# ISO_INPUT.net
KiCad netlist of a schematic drawn in Altium Designer
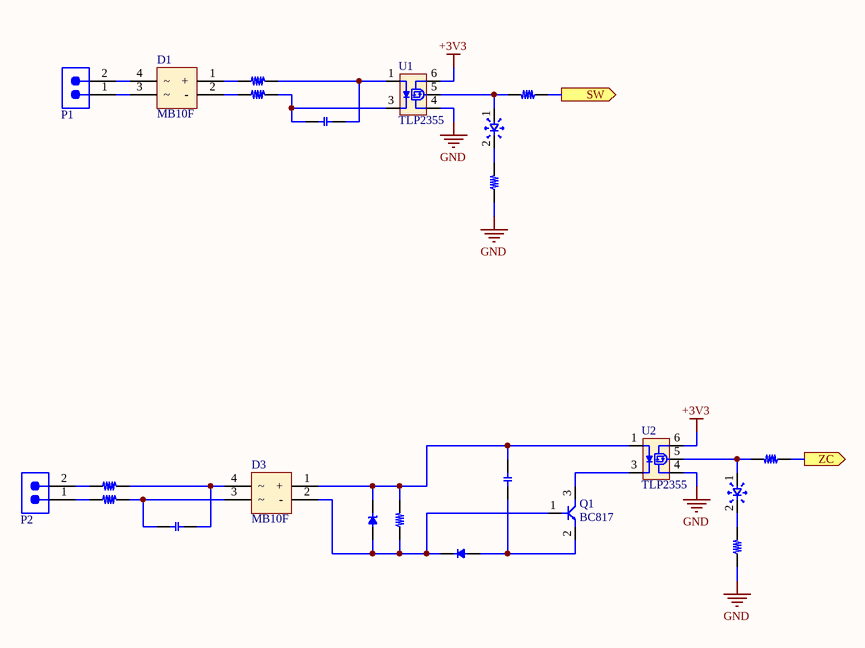
[diagram p0: ISO_INPUT.SchDoc]

(export (version "E")
  (design (tool "Eeschema 10.0.6"))
  (components
    (comp (ref "C1")
      (value "CAP_SMD")
      (footprint "C 1206")
      (libsource (lib "radmehr_library") (part "CAP_SMD"))
    )
    (comp (ref "C2")
      (value "CAP_SMD")
      (footprint "C 1206")
      (libsource (lib "radmehr_library") (part "CAP_SMD"))
    )
    (comp (ref "C3")
      (value "CAP_SMD")
      (footprint "C 1206")
      (libsource (lib "radmehr_library") (part "CAP_SMD"))
    )
    (comp (ref "D1") (value "MB10F") (footprint "MBF") (libsource (lib "radmehr_library") (part "MB10F")))
    (comp (ref "D2")
      (value "LED_SMD")
      (footprint "D 0603")
      (libsource (lib "radmehr_library") (part "LED_SMD"))
    )
    (comp (ref "D3") (value "MB10F") (footprint "MBF") (libsource (lib "radmehr_library") (part "MB10F")))
    (comp (ref "D4")
      (value "LED_SMD")
      (footprint "D 0603")
      (libsource (lib "radmehr_library") (part "LED_SMD"))
    )
    (comp (ref "D5")
      (value "DIOD_SMD_ZENER")
      (footprint "DIOD_SMA")
      (libsource (lib "radmehr_library") (part "DIOD_SMD_ZENER"))
    )
    (comp (ref "D6")
      (value "DIOD_SMD")
      (footprint "DIOD_SMA")
      (libsource (lib "radmehr_library") (part "DIOD_SMD"))
    )
    (comp (ref "P1")
      (value "691321300002")
      (footprint "691321300002")
      (description "WR-TBL Series 321 Vertical PCB Header, Through Hole, pitch 3.81mm, 2p")
      (fields (field (name "MANUFACTURER") "Wurth Elektronik"))
      (libsource (lib "Altium_WR-TBL (rev22a)") (part "691321300002"))
    )
    (comp (ref "P2")
      (value "691321300002")
      (footprint "691321300002")
      (description "WR-TBL Series 321 Vertical PCB Header, Through Hole, pitch 3.81mm, 2p")
      (fields (field (name "MANUFACTURER") "Wurth Elektronik"))
      (libsource (lib "Altium_WR-TBL (rev22a)") (part "691321300002"))
    )
    (comp (ref "Q1")
      (value "BC817")
      (footprint "SOT-23_3_Q")
      (libsource (lib "radmehr_library") (part "BC817"))
    )
    (comp (ref "R1")
      (value "RES_SMD")
      (footprint "R 1206")
      (libsource (lib "radmehr_library") (part "RES_SMD"))
    )
    (comp (ref "R2")
      (value "RES_SMD")
      (footprint "R 1206")
      (libsource (lib "radmehr_library") (part "RES_SMD"))
    )
    (comp (ref "R3")
      (value "RES_SMD")
      (footprint "R 0603")
      (libsource (lib "radmehr_library") (part "RES_SMD"))
    )
    (comp (ref "R4")
      (value "RES_SMD")
      (footprint "R 0603")
      (libsource (lib "radmehr_library") (part "RES_SMD"))
    )
    (comp (ref "R5")
      (value "RES_SMD")
      (footprint "R 0603")
      (libsource (lib "radmehr_library") (part "RES_SMD"))
    )
    (comp (ref "R6")
      (value "RES_SMD")
      (footprint "R 1206")
      (libsource (lib "radmehr_library") (part "RES_SMD"))
    )
    (comp (ref "R7")
      (value "RES_SMD")
      (footprint "R 1206")
      (libsource (lib "radmehr_library") (part "RES_SMD"))
    )
    (comp (ref "R8")
      (value "RES_SMD")
      (footprint "R 1206")
      (libsource (lib "radmehr_library") (part "RES_SMD"))
    )
    (comp (ref "R9")
      (value "RES_SMD")
      (footprint "R 0603")
      (libsource (lib "radmehr_library") (part "RES_SMD"))
    )
    (comp (ref "U1")
      (value "TLP2355")
      (footprint "SOIC-6-5")
      (libsource (lib "radmehr_library") (part "TLP2355"))
    )
    (comp (ref "U2")
      (value "TLP2355")
      (footprint "SOIC-6-5")
      (libsource (lib "radmehr_library") (part "TLP2355"))
    )
  )
  (nets
    (net (code "1") (name "+3V3") (class "Default")
      (node (ref "U1") (pin "6") (pinfunction "VCC_6") (pintype "passive"))
      (node (ref "U2") (pin "6") (pinfunction "VCC_6") (pintype "passive"))
    )
    (net (code "2") (name "/SW") (class "Default")
      (node (ref "R3") (pin "1") (pinfunction "1_1") (pintype "passive"))
    )
    (net (code "3") (name "/ZC") (class "Default")
      (node (ref "R5") (pin "1") (pinfunction "1_1") (pintype "passive"))
    )
    (net (code "4") (name "GND") (class "Default")
      (node (ref "R4") (pin "1") (pinfunction "1_1") (pintype "passive"))
      (node (ref "R9") (pin "1") (pinfunction "1_1") (pintype "passive"))
      (node (ref "U1") (pin "4") (pinfunction "GND_4") (pintype "passive"))
      (node (ref "U2") (pin "4") (pinfunction "GND_4") (pintype "passive"))
    )
    (net (code "5") (name "Net-(C3-Pad1)") (class "Default")
      (node (ref "C3") (pin "1") (pinfunction "1_1") (pintype "passive"))
      (node (ref "D3") (pin "3") (pinfunction "~_3") (pintype "power_in"))
      (node (ref "R7") (pin "2") (pinfunction "2_2") (pintype "passive"))
    )
    (net (code "6") (name "Net-(C3-Pad2)") (class "Default")
      (node (ref "C3") (pin "2") (pinfunction "2_2") (pintype "passive"))
      (node (ref "D3") (pin "4") (pinfunction "~_4") (pintype "power_in"))
      (node (ref "R6") (pin "2") (pinfunction "2_2") (pintype "passive"))
    )
    (net (code "7") (name "Net-(D1-+)") (class "Default")
      (node (ref "D1") (pin "1") (pinfunction "+_1") (pintype "power_in"))
      (node (ref "R1") (pin "1") (pinfunction "1_1") (pintype "passive"))
    )
    (net (code "8") (name "Net-(D1--)") (class "Default")
      (node (ref "D1") (pin "2") (pinfunction "-_2") (pintype "power_in"))
      (node (ref "R2") (pin "1") (pinfunction "1_1") (pintype "passive"))
    )
    (net (code "9") (name "Net-(D1-~-Pad3)") (class "Default")
      (node (ref "D1") (pin "3") (pinfunction "~_3") (pintype "power_in"))
      (node (ref "P1") (pin "1") (pinfunction "1_1") (pintype "passive"))
    )
    (net (code "10") (name "Net-(D1-~-Pad4)") (class "Default")
      (node (ref "D1") (pin "4") (pinfunction "~_4") (pintype "power_in"))
      (node (ref "P1") (pin "2") (pinfunction "2_2") (pintype "passive"))
    )
    (net (code "11") (name "Net-(D2-Pad2)") (class "Default")
      (node (ref "D2") (pin "2") (pintype "passive"))
      (node (ref "R4") (pin "2") (pinfunction "2_2") (pintype "passive"))
    )
    (net (code "12") (name "Net-(D3-+)") (class "Default")
      (node (ref "C2") (pin "1") (pinfunction "1_1") (pintype "passive"))
      (node (ref "D3") (pin "1") (pinfunction "+_1") (pintype "power_in"))
      (node (ref "D5") (pin "2") (pinfunction "2_2") (pintype "passive"))
      (node (ref "R8") (pin "2") (pinfunction "2_2") (pintype "passive"))
      (node (ref "U2") (pin "1") (pinfunction "A_1") (pintype "passive"))
    )
    (net (code "13") (name "Net-(D3--)") (class "Default")
      (node (ref "D3") (pin "2") (pinfunction "-_2") (pintype "power_in"))
      (node (ref "D5") (pin "1") (pinfunction "1_1") (pintype "passive"))
      (node (ref "D6") (pin "2") (pinfunction "2_2") (pintype "passive"))
      (node (ref "Q1") (pin "1") (pinfunction "B_1") (pintype "passive"))
      (node (ref "R8") (pin "1") (pinfunction "1_1") (pintype "passive"))
    )
    (net (code "14") (name "Net-(D4-Pad2)") (class "Default")
      (node (ref "D4") (pin "2") (pintype "passive"))
      (node (ref "R9") (pin "2") (pinfunction "2_2") (pintype "passive"))
    )
    (net (code "15") (name "Net-(P2-Pad1)") (class "Default")
      (node (ref "P2") (pin "1") (pinfunction "1_1") (pintype "passive"))
      (node (ref "R7") (pin "1") (pinfunction "1_1") (pintype "passive"))
    )
    (net (code "16") (name "Net-(P2-Pad2)") (class "Default")
      (node (ref "P2") (pin "2") (pinfunction "2_2") (pintype "passive"))
      (node (ref "R6") (pin "1") (pinfunction "1_1") (pintype "passive"))
    )
    (net (code "17") (name "Net-(Q1-C)") (class "Default")
      (node (ref "Q1") (pin "3") (pinfunction "C_3") (pintype "passive"))
      (node (ref "U2") (pin "3") (pinfunction "K_3") (pintype "passive"))
    )
    (net (code "18") (name "Net-(Q1-E)") (class "Default")
      (node (ref "C2") (pin "2") (pinfunction "2_2") (pintype "passive"))
      (node (ref "D6") (pin "1") (pinfunction "1_1") (pintype "passive"))
      (node (ref "Q1") (pin "2") (pinfunction "E_2") (pintype "passive"))
    )
    (net (code "19") (name "Net-(U1-A)") (class "Default")
      (node (ref "C1") (pin "2") (pinfunction "2_2") (pintype "passive"))
      (node (ref "R1") (pin "2") (pinfunction "2_2") (pintype "passive"))
      (node (ref "U1") (pin "1") (pinfunction "A_1") (pintype "passive"))
    )
    (net (code "20") (name "Net-(U1-K)") (class "Default")
      (node (ref "C1") (pin "1") (pinfunction "1_1") (pintype "passive"))
      (node (ref "R2") (pin "2") (pinfunction "2_2") (pintype "passive"))
      (node (ref "U1") (pin "3") (pinfunction "K_3") (pintype "passive"))
    )
    (net (code "21") (name "Net-(U1-OUT)") (class "Default")
      (node (ref "D2") (pin "1") (pintype "passive"))
      (node (ref "R3") (pin "2") (pinfunction "2_2") (pintype "passive"))
      (node (ref "U1") (pin "5") (pinfunction "OUT_5") (pintype "passive"))
    )
    (net (code "22") (name "Net-(U2-OUT)") (class "Default")
      (node (ref "D4") (pin "1") (pintype "passive"))
      (node (ref "R5") (pin "2") (pinfunction "2_2") (pintype "passive"))
      (node (ref "U2") (pin "5") (pinfunction "OUT_5") (pintype "passive"))
    )
  )
)
